# untitled.net
KiCad netlist of a schematic drawn in EAGLE
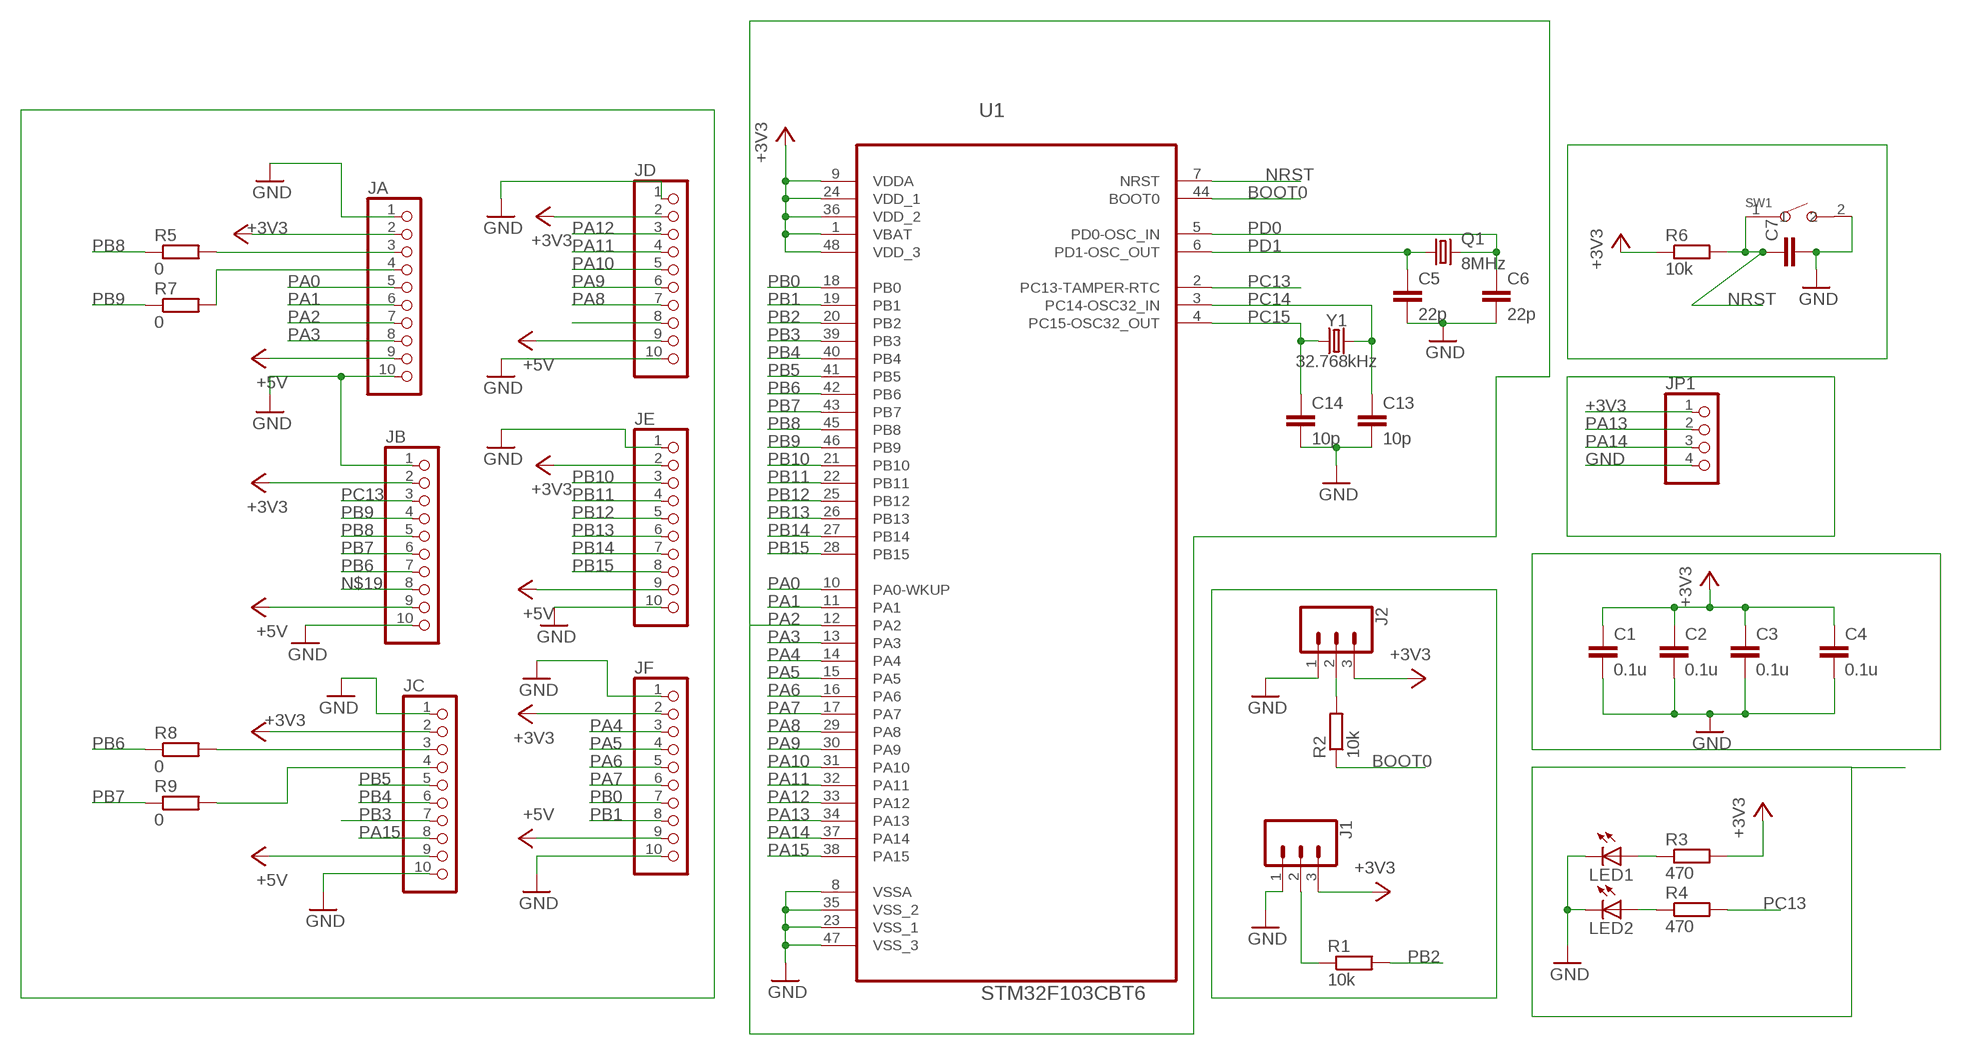
[diagram p0: schematic, sheet 1]

(export (version "E")
  (design (tool "Eeschema 10.0.6"))
  (components
    (comp (ref "C1")
      (value "0.1u")
      (footprint "eagle-import:C0805K")
      (libsource (lib "eagle-import") (part "C-EUC0805K"))
    )
    (comp (ref "C2")
      (value "0.1u")
      (footprint "eagle-import:C0805K")
      (libsource (lib "eagle-import") (part "C-EUC0805K"))
    )
    (comp (ref "C3")
      (value "0.1u")
      (footprint "eagle-import:C0805K")
      (libsource (lib "eagle-import") (part "C-EUC0805K"))
    )
    (comp (ref "C4")
      (value "0.1u")
      (footprint "eagle-import:C0805K")
      (libsource (lib "eagle-import") (part "C-EUC0805K"))
    )
    (comp (ref "C5")
      (value "22p")
      (footprint "eagle-import:C0805K")
      (libsource (lib "eagle-import") (part "C-EUC0805K"))
    )
    (comp (ref "C6")
      (value "22p")
      (footprint "eagle-import:C0805K")
      (libsource (lib "eagle-import") (part "C-EUC0805K"))
    )
    (comp (ref "C7")
      (value "C-EUC0805K")
      (footprint "eagle-import:C0805K")
      (libsource (lib "eagle-import") (part "C-EUC0805K"))
    )
    (comp (ref "C13")
      (value "10p")
      (footprint "eagle-import:C1206K")
      (libsource (lib "eagle-import") (part "C-EUC1206K"))
    )
    (comp (ref "C14")
      (value "10p")
      (footprint "eagle-import:C1206K")
      (libsource (lib "eagle-import") (part "C-EUC1206K"))
    )
    (comp (ref "J1")
      (value "CONN_03")
      (footprint "eagle-import:1X03")
      (libsource (lib "eagle-import") (part "CONN_03"))
    )
    (comp (ref "J2")
      (value "CONN_03")
      (footprint "eagle-import:1X03")
      (libsource (lib "eagle-import") (part "CONN_03"))
    )
    (comp (ref "JA")
      (value "PINHD-1X10")
      (footprint "eagle-import:1X10-BIG")
      (libsource (lib "eagle-import") (part "PINHD-1X10"))
    )
    (comp (ref "JB")
      (value "PINHD-1X10")
      (footprint "eagle-import:1X10-BIG")
      (libsource (lib "eagle-import") (part "PINHD-1X10"))
    )
    (comp (ref "JC")
      (value "PINHD-1X10")
      (footprint "eagle-import:1X10-BIG")
      (libsource (lib "eagle-import") (part "PINHD-1X10"))
    )
    (comp (ref "JD")
      (value "PINHD-1X10")
      (footprint "eagle-import:1X10-BIG")
      (libsource (lib "eagle-import") (part "PINHD-1X10"))
    )
    (comp (ref "JE")
      (value "PINHD-1X10")
      (footprint "eagle-import:1X10-BIG")
      (libsource (lib "eagle-import") (part "PINHD-1X10"))
    )
    (comp (ref "JF")
      (value "PINHD-1X10")
      (footprint "eagle-import:1X10-BIG")
      (libsource (lib "eagle-import") (part "PINHD-1X10"))
    )
    (comp (ref "JP1")
      (value "PINHD-1X4")
      (footprint "eagle-import:1X04")
      (libsource (lib "eagle-import") (part "PINHD-1X4"))
    )
    (comp (ref "LED1")
      (value "LEDCHIPLED_0805")
      (footprint "eagle-import:CHIPLED_0805")
      (libsource (lib "eagle-import") (part "LEDCHIPLED_0805"))
    )
    (comp (ref "LED2")
      (value "LEDCHIPLED_0805")
      (footprint "eagle-import:CHIPLED_0805")
      (libsource (lib "eagle-import") (part "LEDCHIPLED_0805"))
    )
    (comp (ref "Q1")
      (value "8MHz")
      (footprint "eagle-import:HC49_S")
      (libsource (lib "eagle-import") (part "CRYSTALHC49S"))
    )
    (comp (ref "R1")
      (value "10k")
      (footprint "eagle-import:R0805")
      (libsource (lib "eagle-import") (part "R-EU_R0805"))
    )
    (comp (ref "R2")
      (value "10k")
      (footprint "eagle-import:R0805")
      (libsource (lib "eagle-import") (part "R-EU_R0805"))
    )
    (comp (ref "R3")
      (value "470")
      (footprint "eagle-import:R0805")
      (libsource (lib "eagle-import") (part "R-EU_R0805"))
    )
    (comp (ref "R4")
      (value "470")
      (footprint "eagle-import:R0805")
      (libsource (lib "eagle-import") (part "R-EU_R0805"))
    )
    (comp (ref "R5")
      (value "0")
      (footprint "eagle-import:R0805")
      (libsource (lib "eagle-import") (part "R-EU_R0805"))
    )
    (comp (ref "R6")
      (value "10k")
      (footprint "eagle-import:R0805")
      (libsource (lib "eagle-import") (part "R-EU_R0805"))
    )
    (comp (ref "R7")
      (value "0")
      (footprint "eagle-import:R0805")
      (libsource (lib "eagle-import") (part "R-EU_R0805"))
    )
    (comp (ref "R8")
      (value "0")
      (footprint "eagle-import:R0805")
      (libsource (lib "eagle-import") (part "R-EU_R0805"))
    )
    (comp (ref "R9")
      (value "0")
      (footprint "eagle-import:R0805")
      (libsource (lib "eagle-import") (part "R-EU_R0805"))
    )
    (comp (ref "SW1")
      (value "SMD-BUTTON(2P-6.0X3.0X2.5MM)-DHT-1163S")
      (footprint "eagle-import:SW2-4.0-6.0X3.0X2.5MM")
      (libsource (lib "eagle-import") (part "SMD-BUTTON(2P-6.0X3.0X2.5MM)-DHT-1163S"))
    )
    (comp (ref "U1")
      (value "STM32F103CBT6")
      (footprint "eagle-import:QFP50P900X900X160-48N")
      (libsource (lib "eagle-import") (part "STM32F103CBT6"))
    )
    (comp (ref "Y1")
      (value "32.768kHz")
      (footprint "eagle-import:CRYSTAL-SMD-2X6-CYL")
      (libsource (lib "eagle-import") (part "CRYSTAL-32.768KHZSMD-2X6"))
    )
  )
  (nets
    (net (code "1") (name "+3V3") (class "Default")
      (node (ref "C1") (pin "1") (pinfunction "1_1") (pintype "passive"))
      (node (ref "C2") (pin "1") (pinfunction "1_1") (pintype "passive"))
      (node (ref "C3") (pin "1") (pinfunction "1_1") (pintype "passive"))
      (node (ref "C4") (pin "1") (pinfunction "1_1") (pintype "passive"))
      (node (ref "J1") (pin "3") (pinfunction "3_3") (pintype "passive"))
      (node (ref "J2") (pin "3") (pinfunction "3_3") (pintype "passive"))
      (node (ref "JA") (pin "2") (pinfunction "2_2") (pintype "passive"))
      (node (ref "JB") (pin "2") (pinfunction "2_2") (pintype "passive"))
      (node (ref "JC") (pin "2") (pinfunction "2_2") (pintype "passive"))
      (node (ref "JD") (pin "2") (pinfunction "2_2") (pintype "passive"))
      (node (ref "JE") (pin "2") (pinfunction "2_2") (pintype "passive"))
      (node (ref "JF") (pin "2") (pinfunction "2_2") (pintype "passive"))
      (node (ref "JP1") (pin "1") (pinfunction "1_1") (pintype "passive"))
      (node (ref "R3") (pin "2") (pinfunction "2_2") (pintype "passive"))
      (node (ref "R6") (pin "1") (pinfunction "1_1") (pintype "passive"))
      (node (ref "U1") (pin "1") (pinfunction "VBAT_1") (pintype "input"))
      (node (ref "U1") (pin "24") (pinfunction "VDD_1_24") (pintype "bidirectional"))
      (node (ref "U1") (pin "36") (pinfunction "VDD_2_36") (pintype "power_in"))
      (node (ref "U1") (pin "48") (pinfunction "VDD_3_48") (pintype "power_in"))
      (node (ref "U1") (pin "9") (pinfunction "VDDA_9") (pintype "power_in"))
    )
    (net (code "2") (name "+5V") (class "Default")
      (node (ref "JA") (pin "9") (pinfunction "9_9") (pintype "passive"))
      (node (ref "JB") (pin "9") (pinfunction "9_9") (pintype "passive"))
      (node (ref "JC") (pin "9") (pinfunction "9_9") (pintype "passive"))
      (node (ref "JD") (pin "9") (pinfunction "9_9") (pintype "passive"))
      (node (ref "JE") (pin "9") (pinfunction "9_9") (pintype "passive"))
      (node (ref "JF") (pin "9") (pinfunction "9_9") (pintype "passive"))
    )
    (net (code "3") (name "/BOOT0") (class "Default")
      (node (ref "R2") (pin "1") (pinfunction "1_1") (pintype "passive"))
      (node (ref "U1") (pin "44") (pinfunction "BOOT0_44") (pintype "bidirectional"))
    )
    (net (code "4") (name "/N$19") (class "Default")
      (node (ref "JB") (pin "8") (pinfunction "8_8") (pintype "passive"))
    )
    (net (code "5") (name "/NRST") (class "Default")
      (node (ref "C7") (pin "1") (pinfunction "1_1") (pintype "passive"))
      (node (ref "R6") (pin "2") (pinfunction "2_2") (pintype "passive"))
      (node (ref "SW1") (pin "1") (pinfunction "1_1") (pintype "bidirectional"))
      (node (ref "U1") (pin "7") (pinfunction "NRST_7") (pintype "bidirectional"))
    )
    (net (code "6") (name "/PA0") (class "Default")
      (node (ref "JA") (pin "5") (pinfunction "5_5") (pintype "passive"))
      (node (ref "U1") (pin "10") (pinfunction "PA0-WKUP_10") (pintype "bidirectional"))
    )
    (net (code "7") (name "/PA1") (class "Default")
      (node (ref "JA") (pin "6") (pinfunction "6_6") (pintype "passive"))
      (node (ref "U1") (pin "11") (pinfunction "PA1_11") (pintype "bidirectional"))
    )
    (net (code "8") (name "/PA2") (class "Default")
      (node (ref "JA") (pin "7") (pinfunction "7_7") (pintype "passive"))
      (node (ref "U1") (pin "12") (pinfunction "PA2_12") (pintype "bidirectional"))
    )
    (net (code "9") (name "/PA3") (class "Default")
      (node (ref "JA") (pin "8") (pinfunction "8_8") (pintype "passive"))
      (node (ref "U1") (pin "13") (pinfunction "PA3_13") (pintype "bidirectional"))
    )
    (net (code "10") (name "/PA4") (class "Default")
      (node (ref "JF") (pin "3") (pinfunction "3_3") (pintype "passive"))
      (node (ref "U1") (pin "14") (pinfunction "PA4_14") (pintype "bidirectional"))
    )
    (net (code "11") (name "/PA5") (class "Default")
      (node (ref "JF") (pin "4") (pinfunction "4_4") (pintype "passive"))
      (node (ref "U1") (pin "15") (pinfunction "PA5_15") (pintype "bidirectional"))
    )
    (net (code "12") (name "/PA6") (class "Default")
      (node (ref "JF") (pin "5") (pinfunction "5_5") (pintype "passive"))
      (node (ref "U1") (pin "16") (pinfunction "PA6_16") (pintype "bidirectional"))
    )
    (net (code "13") (name "/PA7") (class "Default")
      (node (ref "JF") (pin "6") (pinfunction "6_6") (pintype "passive"))
      (node (ref "U1") (pin "17") (pinfunction "PA7_17") (pintype "bidirectional"))
    )
    (net (code "14") (name "/PA8") (class "Default")
      (node (ref "JD") (pin "7") (pinfunction "7_7") (pintype "passive"))
      (node (ref "U1") (pin "29") (pinfunction "PA8_29") (pintype "bidirectional"))
    )
    (net (code "15") (name "/PA9") (class "Default")
      (node (ref "JD") (pin "6") (pinfunction "6_6") (pintype "passive"))
      (node (ref "U1") (pin "30") (pinfunction "PA9_30") (pintype "bidirectional"))
    )
    (net (code "16") (name "/PA10") (class "Default")
      (node (ref "JD") (pin "5") (pinfunction "5_5") (pintype "passive"))
      (node (ref "U1") (pin "31") (pinfunction "PA10_31") (pintype "bidirectional"))
    )
    (net (code "17") (name "/PA11") (class "Default")
      (node (ref "JD") (pin "4") (pinfunction "4_4") (pintype "passive"))
      (node (ref "U1") (pin "32") (pinfunction "PA11_32") (pintype "power_in"))
    )
    (net (code "18") (name "/PA12") (class "Default")
      (node (ref "JD") (pin "3") (pinfunction "3_3") (pintype "passive"))
      (node (ref "U1") (pin "33") (pinfunction "PA12_33") (pintype "bidirectional"))
    )
    (net (code "19") (name "/PA13") (class "Default")
      (node (ref "JP1") (pin "2") (pinfunction "2_2") (pintype "passive"))
      (node (ref "U1") (pin "34") (pinfunction "PA13_34") (pintype "bidirectional"))
    )
    (net (code "20") (name "/PA14") (class "Default")
      (node (ref "JP1") (pin "3") (pinfunction "3_3") (pintype "passive"))
      (node (ref "U1") (pin "37") (pinfunction "PA14_37") (pintype "bidirectional"))
    )
    (net (code "21") (name "/PA15") (class "Default")
      (node (ref "JC") (pin "8") (pinfunction "8_8") (pintype "passive"))
      (node (ref "U1") (pin "38") (pinfunction "PA15_38") (pintype "bidirectional"))
    )
    (net (code "22") (name "/PB0") (class "Default")
      (node (ref "JF") (pin "7") (pinfunction "7_7") (pintype "passive"))
      (node (ref "U1") (pin "18") (pinfunction "PB0_18") (pintype "bidirectional"))
    )
    (net (code "23") (name "/PB1") (class "Default")
      (node (ref "JF") (pin "8") (pinfunction "8_8") (pintype "passive"))
      (node (ref "U1") (pin "19") (pinfunction "PB1_19") (pintype "bidirectional"))
    )
    (net (code "24") (name "/PB2") (class "Default")
      (node (ref "R1") (pin "2") (pinfunction "2_2") (pintype "passive"))
      (node (ref "U1") (pin "20") (pinfunction "PB2_20") (pintype "bidirectional"))
    )
    (net (code "25") (name "/PB3") (class "Default")
      (node (ref "JC") (pin "7") (pinfunction "7_7") (pintype "passive"))
      (node (ref "U1") (pin "39") (pinfunction "PB3_39") (pintype "bidirectional"))
    )
    (net (code "26") (name "/PB4") (class "Default")
      (node (ref "JC") (pin "6") (pinfunction "6_6") (pintype "passive"))
      (node (ref "U1") (pin "40") (pinfunction "PB4_40") (pintype "bidirectional"))
    )
    (net (code "27") (name "/PB5") (class "Default")
      (node (ref "JC") (pin "5") (pinfunction "5_5") (pintype "passive"))
      (node (ref "U1") (pin "41") (pinfunction "PB5_41") (pintype "bidirectional"))
    )
    (net (code "28") (name "/PB6") (class "Default")
      (node (ref "JB") (pin "7") (pinfunction "7_7") (pintype "passive"))
      (node (ref "R8") (pin "1") (pinfunction "1_1") (pintype "passive"))
      (node (ref "U1") (pin "42") (pinfunction "PB6_42") (pintype "bidirectional"))
    )
    (net (code "29") (name "/PB7") (class "Default")
      (node (ref "JB") (pin "6") (pinfunction "6_6") (pintype "passive"))
      (node (ref "R9") (pin "1") (pinfunction "1_1") (pintype "passive"))
      (node (ref "U1") (pin "43") (pinfunction "PB7_43") (pintype "bidirectional"))
    )
    (net (code "30") (name "/PB8") (class "Default")
      (node (ref "JB") (pin "5") (pinfunction "5_5") (pintype "passive"))
      (node (ref "R5") (pin "1") (pinfunction "1_1") (pintype "passive"))
      (node (ref "U1") (pin "45") (pinfunction "PB8_45") (pintype "bidirectional"))
    )
    (net (code "31") (name "/PB9") (class "Default")
      (node (ref "JB") (pin "4") (pinfunction "4_4") (pintype "passive"))
      (node (ref "R7") (pin "1") (pinfunction "1_1") (pintype "passive"))
      (node (ref "U1") (pin "46") (pinfunction "PB9_46") (pintype "bidirectional"))
    )
    (net (code "32") (name "/PB10") (class "Default")
      (node (ref "JE") (pin "3") (pinfunction "3_3") (pintype "passive"))
      (node (ref "U1") (pin "21") (pinfunction "PB10_21") (pintype "bidirectional"))
    )
    (net (code "33") (name "/PB11") (class "Default")
      (node (ref "JE") (pin "4") (pinfunction "4_4") (pintype "passive"))
      (node (ref "U1") (pin "22") (pinfunction "PB11_22") (pintype "bidirectional"))
    )
    (net (code "34") (name "/PB12") (class "Default")
      (node (ref "JE") (pin "5") (pinfunction "5_5") (pintype "passive"))
      (node (ref "U1") (pin "25") (pinfunction "PB12_25") (pintype "bidirectional"))
    )
    (net (code "35") (name "/PB13") (class "Default")
      (node (ref "JE") (pin "6") (pinfunction "6_6") (pintype "passive"))
      (node (ref "U1") (pin "26") (pinfunction "PB13_26") (pintype "bidirectional"))
    )
    (net (code "36") (name "/PB14") (class "Default")
      (node (ref "JE") (pin "7") (pinfunction "7_7") (pintype "passive"))
      (node (ref "U1") (pin "27") (pinfunction "PB14_27") (pintype "bidirectional"))
    )
    (net (code "37") (name "/PB15") (class "Default")
      (node (ref "JE") (pin "8") (pinfunction "8_8") (pintype "passive"))
      (node (ref "U1") (pin "28") (pinfunction "PB15_28") (pintype "bidirectional"))
    )
    (net (code "38") (name "/PC13") (class "Default")
      (node (ref "JB") (pin "3") (pinfunction "3_3") (pintype "passive"))
      (node (ref "R4") (pin "2") (pinfunction "2_2") (pintype "passive"))
      (node (ref "U1") (pin "2") (pinfunction "PC13-TAMPER-RTC_2") (pintype "bidirectional"))
    )
    (net (code "39") (name "/PC14") (class "Default")
      (node (ref "C13") (pin "1") (pinfunction "1_1") (pintype "passive"))
      (node (ref "U1") (pin "3") (pinfunction "PC14-OSC32_IN_3") (pintype "bidirectional"))
      (node (ref "Y1") (pin "X2") (pinfunction "2_X2") (pintype "passive"))
    )
    (net (code "40") (name "/PC15") (class "Default")
      (node (ref "C14") (pin "1") (pinfunction "1_1") (pintype "passive"))
      (node (ref "U1") (pin "4") (pinfunction "PC15-OSC32_OUT_4") (pintype "bidirectional"))
      (node (ref "Y1") (pin "X1") (pinfunction "1_X1") (pintype "passive"))
    )
    (net (code "41") (name "/PD0") (class "Default")
      (node (ref "C6") (pin "1") (pinfunction "1_1") (pintype "passive"))
      (node (ref "Q1") (pin "2") (pinfunction "2_2") (pintype "passive"))
      (node (ref "U1") (pin "5") (pinfunction "PD0-OSC_IN_5") (pintype "bidirectional"))
    )
    (net (code "42") (name "/PD1") (class "Default")
      (node (ref "C5") (pin "1") (pinfunction "1_1") (pintype "passive"))
      (node (ref "Q1") (pin "1") (pinfunction "1_1") (pintype "passive"))
      (node (ref "U1") (pin "6") (pinfunction "PD1-OSC_OUT_6") (pintype "bidirectional"))
    )
    (net (code "43") (name "GND") (class "Default")
      (node (ref "C1") (pin "2") (pinfunction "2_2") (pintype "passive"))
      (node (ref "C13") (pin "2") (pinfunction "2_2") (pintype "passive"))
      (node (ref "C14") (pin "2") (pinfunction "2_2") (pintype "passive"))
      (node (ref "C2") (pin "2") (pinfunction "2_2") (pintype "passive"))
      (node (ref "C3") (pin "2") (pinfunction "2_2") (pintype "passive"))
      (node (ref "C4") (pin "2") (pinfunction "2_2") (pintype "passive"))
      (node (ref "C5") (pin "2") (pinfunction "2_2") (pintype "passive"))
      (node (ref "C6") (pin "2") (pinfunction "2_2") (pintype "passive"))
      (node (ref "C7") (pin "2") (pinfunction "2_2") (pintype "passive"))
      (node (ref "J1") (pin "1") (pinfunction "1_1") (pintype "passive"))
      (node (ref "J2") (pin "1") (pinfunction "1_1") (pintype "passive"))
      (node (ref "JA") (pin "1") (pinfunction "1_1") (pintype "passive"))
      (node (ref "JA") (pin "10") (pinfunction "10_10") (pintype "passive"))
      (node (ref "JB") (pin "1") (pinfunction "1_1") (pintype "passive"))
      (node (ref "JB") (pin "10") (pinfunction "10_10") (pintype "passive"))
      (node (ref "JC") (pin "1") (pinfunction "1_1") (pintype "passive"))
      (node (ref "JC") (pin "10") (pinfunction "10_10") (pintype "passive"))
      (node (ref "JD") (pin "1") (pinfunction "1_1") (pintype "passive"))
      (node (ref "JD") (pin "10") (pinfunction "10_10") (pintype "passive"))
      (node (ref "JE") (pin "1") (pinfunction "1_1") (pintype "passive"))
      (node (ref "JE") (pin "10") (pinfunction "10_10") (pintype "passive"))
      (node (ref "JF") (pin "1") (pinfunction "1_1") (pintype "passive"))
      (node (ref "JF") (pin "10") (pinfunction "10_10") (pintype "passive"))
      (node (ref "JP1") (pin "4") (pinfunction "4_4") (pintype "passive"))
      (node (ref "LED1") (pin "C") (pinfunction "C_C") (pintype "passive"))
      (node (ref "LED2") (pin "C") (pinfunction "C_C") (pintype "passive"))
      (node (ref "SW1") (pin "2") (pinfunction "2_2") (pintype "bidirectional"))
      (node (ref "U1") (pin "23") (pinfunction "VSS_1_23") (pintype "bidirectional"))
      (node (ref "U1") (pin "35") (pinfunction "VSS_2_35") (pintype "passive"))
      (node (ref "U1") (pin "47") (pinfunction "VSS_3_47") (pintype "passive"))
      (node (ref "U1") (pin "8") (pinfunction "VSSA_8") (pintype "passive"))
    )
    (net (code "44") (name "Net-(J1-Pad2)") (class "Default")
      (node (ref "J1") (pin "2") (pinfunction "2_2") (pintype "passive"))
      (node (ref "R1") (pin "1") (pinfunction "1_1") (pintype "passive"))
    )
    (net (code "45") (name "Net-(J2-Pad2)") (class "Default")
      (node (ref "J2") (pin "2") (pinfunction "2_2") (pintype "passive"))
      (node (ref "R2") (pin "2") (pinfunction "2_2") (pintype "passive"))
    )
    (net (code "46") (name "Net-(JA-Pad3)") (class "Default")
      (node (ref "JA") (pin "3") (pinfunction "3_3") (pintype "passive"))
      (node (ref "R5") (pin "2") (pinfunction "2_2") (pintype "passive"))
    )
    (net (code "47") (name "Net-(JA-Pad4)") (class "Default")
      (node (ref "JA") (pin "4") (pinfunction "4_4") (pintype "passive"))
      (node (ref "R7") (pin "2") (pinfunction "2_2") (pintype "passive"))
    )
    (net (code "48") (name "Net-(JC-Pad3)") (class "Default")
      (node (ref "JC") (pin "3") (pinfunction "3_3") (pintype "passive"))
      (node (ref "R8") (pin "2") (pinfunction "2_2") (pintype "passive"))
    )
    (net (code "49") (name "Net-(JC-Pad4)") (class "Default")
      (node (ref "JC") (pin "4") (pinfunction "4_4") (pintype "passive"))
      (node (ref "R9") (pin "2") (pinfunction "2_2") (pintype "passive"))
    )
    (net (code "50") (name "Net-(LED1-PadA)") (class "Default")
      (node (ref "LED1") (pin "A") (pinfunction "A_A") (pintype "passive"))
      (node (ref "R3") (pin "1") (pinfunction "1_1") (pintype "passive"))
    )
    (net (code "51") (name "Net-(LED2-PadA)") (class "Default")
      (node (ref "LED2") (pin "A") (pinfunction "A_A") (pintype "passive"))
      (node (ref "R4") (pin "1") (pinfunction "1_1") (pintype "passive"))
    )
    (net (code "52") (name "unconnected-(JD-Pad8)") (class "Default")
      (node (ref "JD") (pin "8") (pinfunction "8_8") (pintype "passive"))
    )
  )
)
